# hover.net
KiCad netlist of a schematic drawn in EAGLE
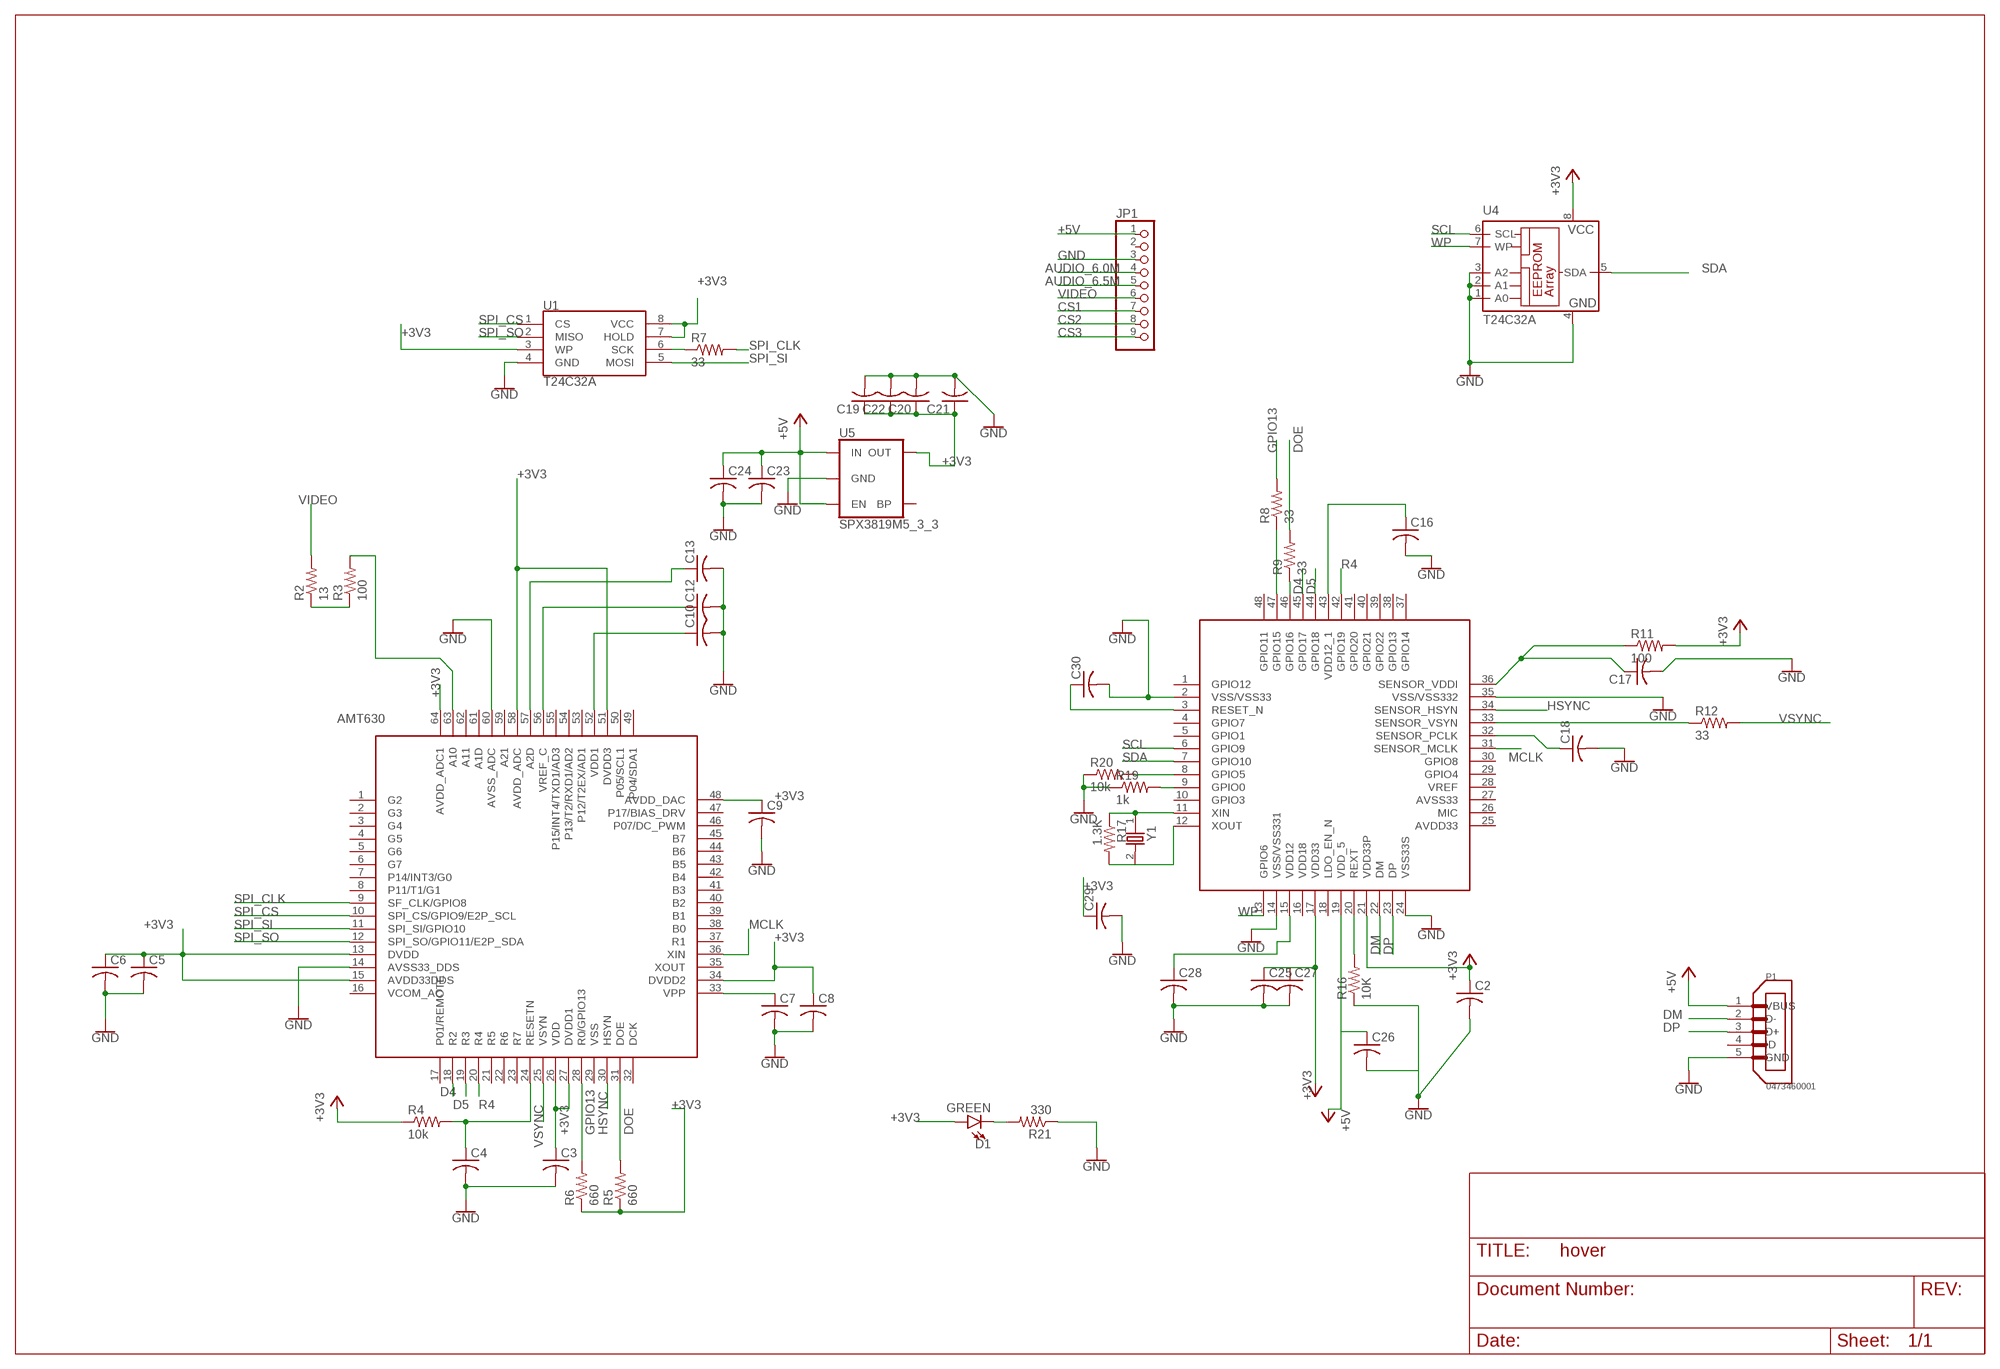
[diagram p0: schematic, sheet 1]

(export (version "E")
  (design (tool "Eeschema 10.0.6"))
  (components
    (comp (ref "C2")
      (value "C-USC0402")
      (footprint "eagle-import:C0402")
      (libsource (lib "eagle-import") (part "C-USC0402"))
    )
    (comp (ref "C3")
      (value "C-USC0402")
      (footprint "eagle-import:C0402")
      (libsource (lib "eagle-import") (part "C-USC0402"))
    )
    (comp (ref "C4")
      (value "C-USC0402")
      (footprint "eagle-import:C0402")
      (libsource (lib "eagle-import") (part "C-USC0402"))
    )
    (comp (ref "C5")
      (value "C-USC0402")
      (footprint "eagle-import:C0402")
      (libsource (lib "eagle-import") (part "C-USC0402"))
    )
    (comp (ref "C6")
      (value "C-USC0402")
      (footprint "eagle-import:C0402")
      (libsource (lib "eagle-import") (part "C-USC0402"))
    )
    (comp (ref "C7")
      (value "C-USC0402")
      (footprint "eagle-import:C0402")
      (libsource (lib "eagle-import") (part "C-USC0402"))
    )
    (comp (ref "C8")
      (value "C-USC0402")
      (footprint "eagle-import:C0402")
      (libsource (lib "eagle-import") (part "C-USC0402"))
    )
    (comp (ref "C9")
      (value "C-USC0402")
      (footprint "eagle-import:C0402")
      (libsource (lib "eagle-import") (part "C-USC0402"))
    )
    (comp (ref "C10")
      (value "C-USC0402")
      (footprint "eagle-import:C0402")
      (libsource (lib "eagle-import") (part "C-USC0402"))
    )
    (comp (ref "C12")
      (value "C-USC0402")
      (footprint "eagle-import:C0402")
      (libsource (lib "eagle-import") (part "C-USC0402"))
    )
    (comp (ref "C13")
      (value "C-USC0402")
      (footprint "eagle-import:C0402")
      (libsource (lib "eagle-import") (part "C-USC0402"))
    )
    (comp (ref "C16")
      (value "C-USC0402")
      (footprint "eagle-import:C0402")
      (libsource (lib "eagle-import") (part "C-USC0402"))
    )
    (comp (ref "C17")
      (value "C-USC0402")
      (footprint "eagle-import:C0402")
      (libsource (lib "eagle-import") (part "C-USC0402"))
    )
    (comp (ref "C18")
      (value "C-USC0402")
      (footprint "eagle-import:C0402")
      (libsource (lib "eagle-import") (part "C-USC0402"))
    )
    (comp (ref "C19")
      (value "C-USC0402")
      (footprint "eagle-import:C0402")
      (libsource (lib "eagle-import") (part "C-USC0402"))
    )
    (comp (ref "C20")
      (value "C-USC0402")
      (footprint "eagle-import:C0402")
      (libsource (lib "eagle-import") (part "C-USC0402"))
    )
    (comp (ref "C21")
      (value "C-USC0402")
      (footprint "eagle-import:C0402")
      (libsource (lib "eagle-import") (part "C-USC0402"))
    )
    (comp (ref "C22")
      (value "C-USC0402")
      (footprint "eagle-import:C0402")
      (libsource (lib "eagle-import") (part "C-USC0402"))
    )
    (comp (ref "C23")
      (value "C-USC0402")
      (footprint "eagle-import:C0402")
      (libsource (lib "eagle-import") (part "C-USC0402"))
    )
    (comp (ref "C24")
      (value "C-USC0402")
      (footprint "eagle-import:C0402")
      (libsource (lib "eagle-import") (part "C-USC0402"))
    )
    (comp (ref "C25")
      (value "C-USC0402")
      (footprint "eagle-import:C0402")
      (libsource (lib "eagle-import") (part "C-USC0402"))
    )
    (comp (ref "C26")
      (value "C-USC0402")
      (footprint "eagle-import:C0402")
      (libsource (lib "eagle-import") (part "C-USC0402"))
    )
    (comp (ref "C27")
      (value "C-USC0402")
      (footprint "eagle-import:C0402")
      (libsource (lib "eagle-import") (part "C-USC0402"))
    )
    (comp (ref "C28")
      (value "C-USC0402")
      (footprint "eagle-import:C0402")
      (libsource (lib "eagle-import") (part "C-USC0402"))
    )
    (comp (ref "C29")
      (value "C-USC0402")
      (footprint "eagle-import:C0402")
      (libsource (lib "eagle-import") (part "C-USC0402"))
    )
    (comp (ref "C30")
      (value "C-USC0402")
      (footprint "eagle-import:C0402")
      (libsource (lib "eagle-import") (part "C-USC0402"))
    )
    (comp (ref "D1")
      (value "GREEN")
      (footprint "eagle-import:LED-0603")
      (libsource (lib "eagle-import") (part "LED-GREEN0603"))
    )
    (comp (ref "JP1")
      (value "PINHD-1X9")
      (footprint "eagle-import:1X09-BIG")
      (libsource (lib "eagle-import") (part "PINHD-1X9"))
    )
    (comp (ref "P1")
      (value "0473460001")
      (footprint "eagle-import:MOLEX_0473460001")
      (fields (field (name "MF") "Weidmuller"))
      (libsource (lib "eagle-import") (part "0473460001"))
    )
    (comp (ref "R2")
      (value "13")
      (footprint "eagle-import:R0402")
      (libsource (lib "eagle-import") (part "R-US_R0402"))
    )
    (comp (ref "R3")
      (value "100")
      (footprint "eagle-import:R0402")
      (libsource (lib "eagle-import") (part "R-US_R0402"))
    )
    (comp (ref "R4")
      (value "10k")
      (footprint "eagle-import:R0402")
      (libsource (lib "eagle-import") (part "R-US_R0402"))
    )
    (comp (ref "R5")
      (value "660")
      (footprint "eagle-import:R0402")
      (libsource (lib "eagle-import") (part "R-US_R0402"))
    )
    (comp (ref "R6")
      (value "660")
      (footprint "eagle-import:R0402")
      (libsource (lib "eagle-import") (part "R-US_R0402"))
    )
    (comp (ref "R7")
      (value "33")
      (footprint "eagle-import:R0402")
      (libsource (lib "eagle-import") (part "R-US_R0402"))
    )
    (comp (ref "R8")
      (value "33")
      (footprint "eagle-import:R0402")
      (libsource (lib "eagle-import") (part "R-US_R0402"))
    )
    (comp (ref "R9")
      (value "33")
      (footprint "eagle-import:R0402")
      (libsource (lib "eagle-import") (part "R-US_R0402"))
    )
    (comp (ref "R11")
      (value "100")
      (footprint "eagle-import:R0402")
      (libsource (lib "eagle-import") (part "R-US_R0402"))
    )
    (comp (ref "R12")
      (value "33")
      (footprint "eagle-import:R0402")
      (libsource (lib "eagle-import") (part "R-US_R0402"))
    )
    (comp (ref "R16")
      (value "10K")
      (footprint "eagle-import:R0402")
      (libsource (lib "eagle-import") (part "R-US_R0402"))
    )
    (comp (ref "R17")
      (value "1.3K")
      (footprint "eagle-import:R0402")
      (libsource (lib "eagle-import") (part "R-US_R0402"))
    )
    (comp (ref "R19")
      (value "1k")
      (footprint "eagle-import:R0402")
      (libsource (lib "eagle-import") (part "R-US_R0402"))
    )
    (comp (ref "R20")
      (value "10k")
      (footprint "eagle-import:R0402")
      (libsource (lib "eagle-import") (part "R-US_R0402"))
    )
    (comp (ref "R21")
      (value "330")
      (footprint "eagle-import:R0402")
      (libsource (lib "eagle-import") (part "R-US_R0402"))
    )
    (comp (ref "U1")
      (value "T24C32A")
      (footprint "eagle-import:SO08-EIAJ")
      (libsource (lib "eagle-import") (part "SPI_FLASH-X25XXSMD1"))
    )
    (comp (ref "U2")
      (value "V399")
      (footprint "eagle-import:LQFP48")
      (libsource (lib "eagle-import") (part "V399"))
    )
    (comp (ref "U3")
      (value "AMT630")
      (footprint "eagle-import:QFP50P1200X1200X160-64N")
      (libsource (lib "eagle-import") (part "AMT630"))
    )
    (comp (ref "U4")
      (value "T24C32A")
      (footprint "eagle-import:SOIC127P600X175-8N")
      (libsource (lib "eagle-import") (part "T24C32A"))
    )
    (comp (ref "U5")
      (value "SPX3819M5_3_3")
      (footprint "eagle-import:SOT23-5")
      (libsource (lib "eagle-import") (part "V_REG_SPX3819-SOT23-5"))
    )
    (comp (ref "Y1")
      (value "ABM3-27.000MHZ-B2-T")
      (footprint "eagle-import:XTAL500X320X130N")
      (fields (field (name "MF") "Abracon"))
      (libsource (lib "eagle-import") (part "ABM3-27.000MHZ-B2-T"))
    )
  )
  (nets
    (net (code "1") (name "+3V3") (class "Default")
      (node (ref "C19") (pin "1") (pinfunction "1_1") (pintype "passive"))
      (node (ref "C2") (pin "1") (pinfunction "1_1") (pintype "passive"))
      (node (ref "C20") (pin "1") (pinfunction "1_1") (pintype "passive"))
      (node (ref "C21") (pin "1") (pinfunction "1_1") (pintype "passive"))
      (node (ref "C22") (pin "1") (pinfunction "1_1") (pintype "passive"))
      (node (ref "C25") (pin "1") (pinfunction "1_1") (pintype "passive"))
      (node (ref "C27") (pin "1") (pinfunction "1_1") (pintype "passive"))
      (node (ref "C29") (pin "1") (pinfunction "1_1") (pintype "passive"))
      (node (ref "C3") (pin "1") (pinfunction "1_1") (pintype "passive"))
      (node (ref "C5") (pin "1") (pinfunction "1_1") (pintype "passive"))
      (node (ref "C6") (pin "1") (pinfunction "1_1") (pintype "passive"))
      (node (ref "C8") (pin "1") (pinfunction "1_1") (pintype "passive"))
      (node (ref "C9") (pin "1") (pinfunction "1_1") (pintype "passive"))
      (node (ref "D1") (pin "A") (pinfunction "A_A") (pintype "passive"))
      (node (ref "R11") (pin "2") (pinfunction "2_2") (pintype "passive"))
      (node (ref "R4") (pin "1") (pinfunction "1_1") (pintype "passive"))
      (node (ref "R5") (pin "1") (pinfunction "1_1") (pintype "passive"))
      (node (ref "R6") (pin "1") (pinfunction "1_1") (pintype "passive"))
      (node (ref "U1") (pin "3") (pinfunction "WP_3") (pintype "bidirectional"))
      (node (ref "U1") (pin "7") (pinfunction "HOLD_7") (pintype "bidirectional"))
      (node (ref "U1") (pin "8") (pinfunction "VCC_8") (pintype "power_in"))
      (node (ref "U2") (pin "17") (pinfunction "VDD33_17") (pintype "bidirectional"))
      (node (ref "U2") (pin "21") (pinfunction "VDD33P_21") (pintype "bidirectional"))
      (node (ref "U3") (pin "13") (pinfunction "DVDD_13") (pintype "bidirectional"))
      (node (ref "U3") (pin "15") (pinfunction "AVDD33DDS_15") (pintype "bidirectional"))
      (node (ref "U3") (pin "26") (pinfunction "VDD_26") (pintype "bidirectional"))
      (node (ref "U3") (pin "27") (pinfunction "DVDD1_27") (pintype "bidirectional"))
      (node (ref "U3") (pin "34") (pinfunction "DVDD2_34") (pintype "bidirectional"))
      (node (ref "U3") (pin "48") (pinfunction "AVDD_DAC_48") (pintype "bidirectional"))
      (node (ref "U3") (pin "51") (pinfunction "DVDD3_51") (pintype "bidirectional"))
      (node (ref "U3") (pin "58") (pinfunction "AVDD_ADC_58") (pintype "bidirectional"))
      (node (ref "U3") (pin "64") (pinfunction "AVDD_ADC1_64") (pintype "bidirectional"))
      (node (ref "U4") (pin "8") (pinfunction "VCC_8") (pintype "power_in"))
      (node (ref "U5") (pin "5") (pinfunction "OUT_5") (pintype "passive"))
    )
    (net (code "2") (name "+5V") (class "Default")
      (node (ref "C23") (pin "1") (pinfunction "1_1") (pintype "passive"))
      (node (ref "C24") (pin "1") (pinfunction "1_1") (pintype "passive"))
      (node (ref "C26") (pin "1") (pinfunction "1_1") (pintype "passive"))
      (node (ref "JP1") (pin "1") (pinfunction "1_1") (pintype "passive"))
      (node (ref "P1") (pin "1") (pinfunction "VBUS_1") (pintype "power_in"))
      (node (ref "U2") (pin "19") (pinfunction "VDD_5_19") (pintype "bidirectional"))
      (node (ref "U5") (pin "1") (pinfunction "IN_1") (pintype "input"))
      (node (ref "U5") (pin "3") (pinfunction "EN_3") (pintype "input"))
    )
    (net (code "3") (name "/AUDIO_6.0M") (class "Default")
      (node (ref "JP1") (pin "4") (pinfunction "4_4") (pintype "passive"))
    )
    (net (code "4") (name "/AUDIO_6.5M") (class "Default")
      (node (ref "JP1") (pin "5") (pinfunction "5_5") (pintype "passive"))
    )
    (net (code "5") (name "/CS1") (class "Default")
      (node (ref "JP1") (pin "7") (pinfunction "7_7") (pintype "passive"))
    )
    (net (code "6") (name "/CS2") (class "Default")
      (node (ref "JP1") (pin "8") (pinfunction "8_8") (pintype "passive"))
    )
    (net (code "7") (name "/CS3") (class "Default")
      (node (ref "JP1") (pin "9") (pinfunction "9_9") (pintype "passive"))
    )
    (net (code "8") (name "/D4") (class "Default")
      (node (ref "U2") (pin "45") (pinfunction "GPIO17_45") (pintype "bidirectional"))
      (node (ref "U3") (pin "18") (pinfunction "R2_18") (pintype "bidirectional"))
    )
    (net (code "9") (name "/D5") (class "Default")
      (node (ref "U2") (pin "44") (pinfunction "GPIO18_44") (pintype "bidirectional"))
      (node (ref "U3") (pin "19") (pinfunction "R3_19") (pintype "bidirectional"))
    )
    (net (code "10") (name "/DM") (class "Default")
      (node (ref "P1") (pin "2") (pinfunction "D-_2") (pintype "bidirectional"))
      (node (ref "U2") (pin "22") (pinfunction "DM_22") (pintype "bidirectional"))
    )
    (net (code "11") (name "/DOE") (class "Default")
      (node (ref "R5") (pin "2") (pinfunction "2_2") (pintype "passive"))
      (node (ref "R9") (pin "2") (pinfunction "2_2") (pintype "passive"))
      (node (ref "U3") (pin "31") (pinfunction "DOE_31") (pintype "bidirectional"))
    )
    (net (code "12") (name "/DP") (class "Default")
      (node (ref "P1") (pin "3") (pinfunction "D+_3") (pintype "bidirectional"))
      (node (ref "U2") (pin "23") (pinfunction "DP_23") (pintype "bidirectional"))
    )
    (net (code "13") (name "/GPIO13") (class "Default")
      (node (ref "R6") (pin "2") (pinfunction "2_2") (pintype "passive"))
      (node (ref "R8") (pin "2") (pinfunction "2_2") (pintype "passive"))
      (node (ref "U3") (pin "28") (pinfunction "R0/GPIO13_28") (pintype "bidirectional"))
    )
    (net (code "14") (name "/HSYNC") (class "Default")
      (node (ref "U2") (pin "34") (pinfunction "SENSOR_HSYN_34") (pintype "bidirectional"))
      (node (ref "U3") (pin "30") (pinfunction "HSYN_30") (pintype "bidirectional"))
    )
    (net (code "15") (name "/MCLK") (class "Default")
      (node (ref "U2") (pin "31") (pinfunction "SENSOR_MCLK_31") (pintype "bidirectional"))
      (node (ref "U3") (pin "36") (pinfunction "XIN_36") (pintype "bidirectional"))
    )
    (net (code "16") (name "/R4") (class "Default")
      (node (ref "U2") (pin "42") (pinfunction "GPIO19_42") (pintype "bidirectional"))
      (node (ref "U3") (pin "20") (pinfunction "R4_20") (pintype "bidirectional"))
    )
    (net (code "17") (name "/SCL") (class "Default")
      (node (ref "U2") (pin "6") (pinfunction "GPIO9_6") (pintype "bidirectional"))
      (node (ref "U4") (pin "6") (pinfunction "SCL_6") (pintype "input"))
    )
    (net (code "18") (name "/SDA") (class "Default")
      (node (ref "U2") (pin "7") (pinfunction "GPIO10_7") (pintype "bidirectional"))
      (node (ref "U4") (pin "5") (pinfunction "SDA_5") (pintype "bidirectional"))
    )
    (net (code "19") (name "/SPI_CLK") (class "Default")
      (node (ref "R7") (pin "2") (pinfunction "2_2") (pintype "passive"))
      (node (ref "U3") (pin "9") (pinfunction "SF_CLK/GPIO8_9") (pintype "bidirectional"))
    )
    (net (code "20") (name "/SPI_CS") (class "Default")
      (node (ref "U1") (pin "1") (pinfunction "CS_1") (pintype "bidirectional"))
      (node (ref "U3") (pin "10") (pinfunction "SPI_CS/GPIO9/E2P_SCL_10") (pintype "bidirectional"))
    )
    (net (code "21") (name "/SPI_SI") (class "Default")
      (node (ref "U1") (pin "5") (pinfunction "MOSI_5") (pintype "bidirectional"))
      (node (ref "U3") (pin "11") (pinfunction "SPI_SI/GPIO10_11") (pintype "bidirectional"))
    )
    (net (code "22") (name "/SPI_SO") (class "Default")
      (node (ref "U1") (pin "2") (pinfunction "MISO_2") (pintype "bidirectional"))
      (node (ref "U3") (pin "12") (pinfunction "SPI_SO/GPIO11/E2P_SDA_12") (pintype "bidirectional"))
    )
    (net (code "23") (name "/VIDEO") (class "Default")
      (node (ref "JP1") (pin "6") (pinfunction "6_6") (pintype "passive"))
      (node (ref "R2") (pin "2") (pinfunction "2_2") (pintype "passive"))
    )
    (net (code "24") (name "/VSYNC") (class "Default")
      (node (ref "R12") (pin "2") (pinfunction "2_2") (pintype "passive"))
      (node (ref "U3") (pin "25") (pinfunction "VSYN_25") (pintype "bidirectional"))
    )
    (net (code "25") (name "/WP") (class "Default")
      (node (ref "U2") (pin "13") (pinfunction "GPIO6_13") (pintype "bidirectional"))
      (node (ref "U4") (pin "7") (pinfunction "WP_7") (pintype "input"))
    )
    (net (code "26") (name "GND") (class "Default")
      (node (ref "C10") (pin "2") (pinfunction "2_2") (pintype "passive"))
      (node (ref "C12") (pin "2") (pinfunction "2_2") (pintype "passive"))
      (node (ref "C13") (pin "2") (pinfunction "2_2") (pintype "passive"))
      (node (ref "C16") (pin "2") (pinfunction "2_2") (pintype "passive"))
      (node (ref "C17") (pin "2") (pinfunction "2_2") (pintype "passive"))
      (node (ref "C18") (pin "2") (pinfunction "2_2") (pintype "passive"))
      (node (ref "C19") (pin "2") (pinfunction "2_2") (pintype "passive"))
      (node (ref "C2") (pin "2") (pinfunction "2_2") (pintype "passive"))
      (node (ref "C20") (pin "2") (pinfunction "2_2") (pintype "passive"))
      (node (ref "C21") (pin "2") (pinfunction "2_2") (pintype "passive"))
      (node (ref "C22") (pin "2") (pinfunction "2_2") (pintype "passive"))
      (node (ref "C23") (pin "2") (pinfunction "2_2") (pintype "passive"))
      (node (ref "C24") (pin "2") (pinfunction "2_2") (pintype "passive"))
      (node (ref "C25") (pin "2") (pinfunction "2_2") (pintype "passive"))
      (node (ref "C26") (pin "2") (pinfunction "2_2") (pintype "passive"))
      (node (ref "C27") (pin "2") (pinfunction "2_2") (pintype "passive"))
      (node (ref "C28") (pin "2") (pinfunction "2_2") (pintype "passive"))
      (node (ref "C29") (pin "2") (pinfunction "2_2") (pintype "passive"))
      (node (ref "C3") (pin "2") (pinfunction "2_2") (pintype "passive"))
      (node (ref "C30") (pin "2") (pinfunction "2_2") (pintype "passive"))
      (node (ref "C4") (pin "2") (pinfunction "2_2") (pintype "passive"))
      (node (ref "C5") (pin "2") (pinfunction "2_2") (pintype "passive"))
      (node (ref "C6") (pin "2") (pinfunction "2_2") (pintype "passive"))
      (node (ref "C7") (pin "2") (pinfunction "2_2") (pintype "passive"))
      (node (ref "C8") (pin "2") (pinfunction "2_2") (pintype "passive"))
      (node (ref "C9") (pin "2") (pinfunction "2_2") (pintype "passive"))
      (node (ref "JP1") (pin "3") (pinfunction "3_3") (pintype "passive"))
      (node (ref "P1") (pin "5") (pinfunction "GND_5") (pintype "passive"))
      (node (ref "R16") (pin "1") (pinfunction "1_1") (pintype "passive"))
      (node (ref "R19") (pin "1") (pinfunction "1_1") (pintype "passive"))
      (node (ref "R20") (pin "1") (pinfunction "1_1") (pintype "passive"))
      (node (ref "R21") (pin "1") (pinfunction "1_1") (pintype "passive"))
      (node (ref "U1") (pin "4") (pinfunction "GND_4") (pintype "power_in"))
      (node (ref "U2") (pin "14") (pinfunction "VSS/VSS331_14") (pintype "bidirectional"))
      (node (ref "U2") (pin "2") (pinfunction "VSS/VSS33_2") (pintype "bidirectional"))
      (node (ref "U2") (pin "24") (pinfunction "VSS33S_24") (pintype "bidirectional"))
      (node (ref "U2") (pin "35") (pinfunction "VSS/VSS332_35") (pintype "bidirectional"))
      (node (ref "U3") (pin "14") (pinfunction "AVSS33_DDS_14") (pintype "bidirectional"))
      (node (ref "U3") (pin "60") (pinfunction "AVSS_ADC_60") (pintype "bidirectional"))
      (node (ref "U4") (pin "1") (pinfunction "A0_1") (pintype "input"))
      (node (ref "U4") (pin "2") (pinfunction "A1_2") (pintype "input"))
      (node (ref "U4") (pin "3") (pinfunction "A2_3") (pintype "input"))
      (node (ref "U4") (pin "4") (pinfunction "GND_4") (pintype "power_in"))
      (node (ref "U5") (pin "2") (pinfunction "GND_2") (pintype "input"))
    )
    (net (code "27") (name "Net-(D1-PadC)") (class "Default")
      (node (ref "D1") (pin "C") (pinfunction "C_C") (pintype "passive"))
      (node (ref "R21") (pin "2") (pinfunction "2_2") (pintype "passive"))
    )
    (net (code "28") (name "Net-(R2-Pad1)") (class "Default")
      (node (ref "R2") (pin "1") (pinfunction "1_1") (pintype "passive"))
      (node (ref "R3") (pin "1") (pinfunction "1_1") (pintype "passive"))
    )
    (net (code "29") (name "Net-(U1-SCK)") (class "Default")
      (node (ref "R7") (pin "1") (pinfunction "1_1") (pintype "passive"))
      (node (ref "U1") (pin "6") (pinfunction "SCK_6") (pintype "bidirectional"))
    )
    (net (code "30") (name "Net-(U2-GPIO0)") (class "Default")
      (node (ref "R19") (pin "2") (pinfunction "2_2") (pintype "passive"))
      (node (ref "U2") (pin "9") (pinfunction "GPIO0_9") (pintype "bidirectional"))
    )
    (net (code "31") (name "Net-(U2-GPIO5)") (class "Default")
      (node (ref "R20") (pin "2") (pinfunction "2_2") (pintype "passive"))
      (node (ref "U2") (pin "8") (pinfunction "GPIO5_8") (pintype "bidirectional"))
    )
    (net (code "32") (name "Net-(U2-GPIO15)") (class "Default")
      (node (ref "R8") (pin "1") (pinfunction "1_1") (pintype "passive"))
      (node (ref "U2") (pin "47") (pinfunction "GPIO15_47") (pintype "bidirectional"))
    )
    (net (code "33") (name "Net-(U2-GPIO16)") (class "Default")
      (node (ref "R9") (pin "1") (pinfunction "1_1") (pintype "passive"))
      (node (ref "U2") (pin "46") (pinfunction "GPIO16_46") (pintype "bidirectional"))
    )
    (net (code "34") (name "Net-(U2-RESET_N)") (class "Default")
      (node (ref "C30") (pin "1") (pinfunction "1_1") (pintype "passive"))
      (node (ref "U2") (pin "3") (pinfunction "RESET_N_3") (pintype "bidirectional"))
    )
    (net (code "35") (name "Net-(U2-REXT)") (class "Default")
      (node (ref "R16") (pin "2") (pinfunction "2_2") (pintype "passive"))
      (node (ref "U2") (pin "20") (pinfunction "REXT_20") (pintype "bidirectional"))
    )
    (net (code "36") (name "Net-(U2-SENSOR_PCLK)") (class "Default")
      (node (ref "C18") (pin "1") (pinfunction "1_1") (pintype "passive"))
      (node (ref "U2") (pin "32") (pinfunction "SENSOR_PCLK_32") (pintype "bidirectional"))
    )
    (net (code "37") (name "Net-(U2-SENSOR_VDDI)") (class "Default")
      (node (ref "C17") (pin "1") (pinfunction "1_1") (pintype "passive"))
      (node (ref "R11") (pin "1") (pinfunction "1_1") (pintype "passive"))
      (node (ref "U2") (pin "36") (pinfunction "SENSOR_VDDI_36") (pintype "bidirectional"))
    )
    (net (code "38") (name "Net-(U2-SENSOR_VSYN)") (class "Default")
      (node (ref "R12") (pin "1") (pinfunction "1_1") (pintype "passive"))
      (node (ref "U2") (pin "33") (pinfunction "SENSOR_VSYN_33") (pintype "bidirectional"))
    )
    (net (code "39") (name "Net-(U2-VDD12)") (class "Default")
      (node (ref "C28") (pin "1") (pinfunction "1_1") (pintype "passive"))
      (node (ref "U2") (pin "15") (pinfunction "VDD12_15") (pintype "bidirectional"))
    )
    (net (code "40") (name "Net-(U2-VDD12_1)") (class "Default")
      (node (ref "C16") (pin "1") (pinfunction "1_1") (pintype "passive"))
      (node (ref "U2") (pin "43") (pinfunction "VDD12_1_43") (pintype "bidirectional"))
    )
    (net (code "41") (name "Net-(U2-XIN)") (class "Default")
      (node (ref "R17") (pin "1") (pinfunction "1_1") (pintype "passive"))
      (node (ref "U2") (pin "11") (pinfunction "XIN_11") (pintype "bidirectional"))
      (node (ref "Y1") (pin "1") (pinfunction "1_1") (pintype "passive"))
    )
    (net (code "42") (name "Net-(U2-XOUT)") (class "Default")
      (node (ref "R17") (pin "2") (pinfunction "2_2") (pintype "passive"))
      (node (ref "U2") (pin "12") (pinfunction "XOUT_12") (pintype "bidirectional"))
      (node (ref "Y1") (pin "2") (pinfunction "2_2") (pintype "passive"))
    )
    (net (code "43") (name "Net-(U3-A2D)") (class "Default")
      (node (ref "C13") (pin "1") (pinfunction "1_1") (pintype "passive"))
      (node (ref "U3") (pin "57") (pinfunction "A2D_57") (pintype "bidirectional"))
    )
    (net (code "44") (name "Net-(U3-A10)") (class "Default")
      (node (ref "R3") (pin "2") (pinfunction "2_2") (pintype "passive"))
      (node (ref "U3") (pin "63") (pinfunction "A10_63") (pintype "bidirectional"))
    )
    (net (code "45") (name "Net-(U3-RESETN)") (class "Default")
      (node (ref "C4") (pin "1") (pinfunction "1_1") (pintype "passive"))
      (node (ref "R4") (pin "2") (pinfunction "2_2") (pintype "passive"))
      (node (ref "U3") (pin "24") (pinfunction "RESETN_24") (pintype "bidirectional"))
    )
    (net (code "46") (name "Net-(U3-VDD1)") (class "Default")
      (node (ref "C10") (pin "1") (pinfunction "1_1") (pintype "passive"))
      (node (ref "U3") (pin "52") (pinfunction "VDD1_52") (pintype "bidirectional"))
    )
    (net (code "47") (name "Net-(U3-VPP)") (class "Default")
      (node (ref "C7") (pin "1") (pinfunction "1_1") (pintype "passive"))
      (node (ref "U3") (pin "33") (pinfunction "VPP_33") (pintype "bidirectional"))
    )
    (net (code "48") (name "Net-(U3-VREF_C)") (class "Default")
      (node (ref "C12") (pin "1") (pinfunction "1_1") (pintype "passive"))
      (node (ref "U3") (pin "56") (pinfunction "VREF_C_56") (pintype "bidirectional"))
    )
    (net (code "49") (name "unconnected-(JP1-Pad2)") (class "Default")
      (node (ref "JP1") (pin "2") (pinfunction "2_2") (pintype "passive"))
    )
    (net (code "50") (name "unconnected-(P1-ID-Pad4)") (class "Default")
      (node (ref "P1") (pin "4") (pinfunction "ID_4") (pintype "bidirectional"))
    )
    (net (code "51") (name "unconnected-(U2-AVDD33-Pad25)") (class "Default")
      (node (ref "U2") (pin "25") (pinfunction "AVDD33_25") (pintype "bidirectional"))
    )
    (net (code "52") (name "unconnected-(U2-AVSS33-Pad27)") (class "Default")
      (node (ref "U2") (pin "27") (pinfunction "AVSS33_27") (pintype "bidirectional"))
    )
    (net (code "53") (name "unconnected-(U2-GPIO1-Pad5)") (class "Default")
      (node (ref "U2") (pin "5") (pinfunction "GPIO1_5") (pintype "bidirectional"))
    )
    (net (code "54") (name "unconnected-(U2-GPIO3-Pad10)") (class "Default")
      (node (ref "U2") (pin "10") (pinfunction "GPIO3_10") (pintype "bidirectional"))
    )
    (net (code "55") (name "unconnected-(U2-GPIO4-Pad29)") (class "Default")
      (node (ref "U2") (pin "29") (pinfunction "GPIO4_29") (pintype "bidirectional"))
    )
    (net (code "56") (name "unconnected-(U2-GPIO7-Pad4)") (class "Default")
      (node (ref "U2") (pin "4") (pinfunction "GPIO7_4") (pintype "bidirectional"))
    )
    (net (code "57") (name "unconnected-(U2-GPIO8-Pad30)") (class "Default")
      (node (ref "U2") (pin "30") (pinfunction "GPIO8_30") (pintype "bidirectional"))
    )
    (net (code "58") (name "unconnected-(U2-GPIO11-Pad48)") (class "Default")
      (node (ref "U2") (pin "48") (pinfunction "GPIO11_48") (pintype "bidirectional"))
    )
    (net (code "59") (name "unconnected-(U2-GPIO12-Pad1)") (class "Default")
      (node (ref "U2") (pin "1") (pinfunction "GPIO12_1") (pintype "bidirectional"))
    )
    (net (code "60") (name "unconnected-(U2-GPIO13-Pad38)") (class "Default")
      (node (ref "U2") (pin "38") (pinfunction "GPIO13_38") (pintype "bidirectional"))
    )
    (net (code "61") (name "unconnected-(U2-GPIO14-Pad37)") (class "Default")
      (node (ref "U2") (pin "37") (pinfunction "GPIO14_37") (pintype "bidirectional"))
    )
    (net (code "62") (name "unconnected-(U2-GPIO20-Pad41)") (class "Default")
      (node (ref "U2") (pin "41") (pinfunction "GPIO20_41") (pintype "bidirectional"))
    )
    (net (code "63") (name "unconnected-(U2-GPIO21-Pad40)") (class "Default")
      (node (ref "U2") (pin "40") (pinfunction "GPIO21_40") (pintype "bidirectional"))
    )
    (net (code "64") (name "unconnected-(U2-GPIO22-Pad39)") (class "Default")
      (node (ref "U2") (pin "39") (pinfunction "GPIO22_39") (pintype "bidirectional"))
    )
    (net (code "65") (name "unconnected-(U2-LDO_EN_N-Pad18)") (class "Default")
      (node (ref "U2") (pin "18") (pinfunction "LDO_EN_N_18") (pintype "bidirectional"))
    )
    (net (code "66") (name "unconnected-(U2-MIC-Pad26)") (class "Default")
      (node (ref "U2") (pin "26") (pinfunction "MIC_26") (pintype "bidirectional"))
    )
    (net (code "67") (name "unconnected-(U2-VDD18-Pad16)") (class "Default")
      (node (ref "U2") (pin "16") (pinfunction "VDD18_16") (pintype "bidirectional"))
    )
    (net (code "68") (name "unconnected-(U2-VREF-Pad28)") (class "Default")
      (node (ref "U2") (pin "28") (pinfunction "VREF_28") (pintype "bidirectional"))
    )
    (net (code "69") (name "unconnected-(U3-A1D-Pad61)") (class "Default")
      (node (ref "U3") (pin "61") (pinfunction "A1D_61") (pintype "bidirectional"))
    )
    (net (code "70") (name "unconnected-(U3-A11-Pad62)") (class "Default")
      (node (ref "U3") (pin "62") (pinfunction "A11_62") (pintype "bidirectional"))
    )
    (net (code "71") (name "unconnected-(U3-A21-Pad59)") (class "Default")
      (node (ref "U3") (pin "59") (pinfunction "A21_59") (pintype "bidirectional"))
    )
    (net (code "72") (name "unconnected-(U3-B0-Pad38)") (class "Default")
      (node (ref "U3") (pin "38") (pinfunction "B0_38") (pintype "bidirectional"))
    )
    (net (code "73") (name "unconnected-(U3-B1-Pad39)") (class "Default")
      (node (ref "U3") (pin "39") (pinfunction "B1_39") (pintype "bidirectional"))
    )
    (net (code "74") (name "unconnected-(U3-B2-Pad40)") (class "Default")
      (node (ref "U3") (pin "40") (pinfunction "B2_40") (pintype "bidirectional"))
    )
    (net (code "75") (name "unconnected-(U3-B3-Pad41)") (class "Default")
      (node (ref "U3") (pin "41") (pinfunction "B3_41") (pintype "bidirectional"))
    )
    (net (code "76") (name "unconnected-(U3-B4-Pad42)") (class "Default")
      (node (ref "U3") (pin "42") (pinfunction "B4_42") (pintype "bidirectional"))
    )
    (net (code "77") (name "unconnected-(U3-B5-Pad43)") (class "Default")
      (node (ref "U3") (pin "43") (pinfunction "B5_43") (pintype "bidirectional"))
    )
    (net (code "78") (name "unconnected-(U3-B6-Pad44)") (class "Default")
      (node (ref "U3") (pin "44") (pinfunction "B6_44") (pintype "bidirectional"))
    )
    (net (code "79") (name "unconnected-(U3-B7-Pad45)") (class "Default")
      (node (ref "U3") (pin "45") (pinfunction "B7_45") (pintype "bidirectional"))
    )
    (net (code "80") (name "unconnected-(U3-DCK-Pad32)") (class "Default")
      (node (ref "U3") (pin "32") (pinfunction "DCK_32") (pintype "bidirectional"))
    )
    (net (code "81") (name "unconnected-(U3-G2-Pad1)") (class "Default")
      (node (ref "U3") (pin "1") (pinfunction "G2_1") (pintype "bidirectional"))
    )
    (net (code "82") (name "unconnected-(U3-G3-Pad2)") (class "Default")
      (node (ref "U3") (pin "2") (pinfunction "G3_2") (pintype "bidirectional"))
    )
    (net (code "83") (name "unconnected-(U3-G4-Pad3)") (class "Default")
      (node (ref "U3") (pin "3") (pinfunction "G4_3") (pintype "bidirectional"))
    )
    (net (code "84") (name "unconnected-(U3-G5-Pad4)") (class "Default")
      (node (ref "U3") (pin "4") (pinfunction "G5_4") (pintype "bidirectional"))
    )
    (net (code "85") (name "unconnected-(U3-G6-Pad5)") (class "Default")
      (node (ref "U3") (pin "5") (pinfunction "G6_5") (pintype "bidirectional"))
    )
    (net (code "86") (name "unconnected-(U3-G7-Pad6)") (class "Default")
      (node (ref "U3") (pin "6") (pinfunction "G7_6") (pintype "bidirectional"))
    )
    (net (code "87") (name "unconnected-(U3-P01{slash}REMOTE-Pad17)") (class "Default")
      (node (ref "U3") (pin "17") (pinfunction "P01/REMOTE_17") (pintype "bidirectional"))
    )
    (net (code "88") (name "unconnected-(U3-P04{slash}SDA1-Pad49)") (class "Default")
      (node (ref "U3") (pin "49") (pinfunction "P04/SDA1_49") (pintype "bidirectional"))
    )
    (net (code "89") (name "unconnected-(U3-P05{slash}SCL1-Pad50)") (class "Default")
      (node (ref "U3") (pin "50") (pinfunction "P05/SCL1_50") (pintype "bidirectional"))
    )
    (net (code "90") (name "unconnected-(U3-P07{slash}DC_PWM-Pad46)") (class "Default")
      (node (ref "U3") (pin "46") (pinfunction "P07/DC_PWM_46") (pintype "bidirectional"))
    )
    (net (code "91") (name "unconnected-(U3-P11{slash}T1{slash}G1-Pad8)") (class "Default")
      (node (ref "U3") (pin "8") (pinfunction "P11/T1/G1_8") (pintype "bidirectional"))
    )
    (net (code "92") (name "unconnected-(U3-P12{slash}T2EX{slash}AD1-Pad53)") (class "Default")
      (node (ref "U3") (pin "53") (pinfunction "P12/T2EX/AD1_53") (pintype "bidirectional"))
    )
    (net (code "93") (name "unconnected-(U3-P13{slash}T2{slash}RXD1{slash}AD2-Pad54)") (class "Default")
      (node (ref "U3") (pin "54") (pinfunction "P13/T2/RXD1/AD2_54") (pintype "bidirectional"))
    )
    (net (code "94") (name "unconnected-(U3-P14{slash}INT3{slash}G0-Pad7)") (class "Default")
      (node (ref "U3") (pin "7") (pinfunction "P14/INT3/G0_7") (pintype "bidirectional"))
    )
    (net (code "95") (name "unconnected-(U3-P15{slash}INT4{slash}TXD1{slash}AD3-Pad55)") (class "Default")
      (node (ref "U3") (pin "55") (pinfunction "P15/INT4/TXD1/AD3_55") (pintype "bidirectional"))
    )
    (net (code "96") (name "unconnected-(U3-P17{slash}BIAS_DRV-Pad47)") (class "Default")
      (node (ref "U3") (pin "47") (pinfunction "P17/BIAS_DRV_47") (pintype "bidirectional"))
    )
    (net (code "97") (name "unconnected-(U3-R1-Pad37)") (class "Default")
      (node (ref "U3") (pin "37") (pinfunction "R1_37") (pintype "bidirectional"))
    )
    (net (code "98") (name "unconnected-(U3-R5-Pad21)") (class "Default")
      (node (ref "U3") (pin "21") (pinfunction "R5_21") (pintype "bidirectional"))
    )
    (net (code "99") (name "unconnected-(U3-R6-Pad22)") (class "Default")
      (node (ref "U3") (pin "22") (pinfunction "R6_22") (pintype "bidirectional"))
    )
    (net (code "100") (name "unconnected-(U3-R7-Pad23)") (class "Default")
      (node (ref "U3") (pin "23") (pinfunction "R7_23") (pintype "bidirectional"))
    )
    (net (code "101") (name "unconnected-(U3-VCOM_AC-Pad16)") (class "Default")
      (node (ref "U3") (pin "16") (pinfunction "VCOM_AC_16") (pintype "bidirectional"))
    )
    (net (code "102") (name "unconnected-(U3-VSS-Pad29)") (class "Default")
      (node (ref "U3") (pin "29") (pinfunction "VSS_29") (pintype "bidirectional"))
    )
    (net (code "103") (name "unconnected-(U3-XOUT-Pad35)") (class "Default")
      (node (ref "U3") (pin "35") (pinfunction "XOUT_35") (pintype "bidirectional"))
    )
    (net (code "104") (name "unconnected-(U5-BP-Pad4)") (class "Default")
      (node (ref "U5") (pin "4") (pinfunction "BP_4") (pintype "input"))
    )
  )
)
